# PR9001.net
KiCad netlist of a schematic drawn in EAGLE
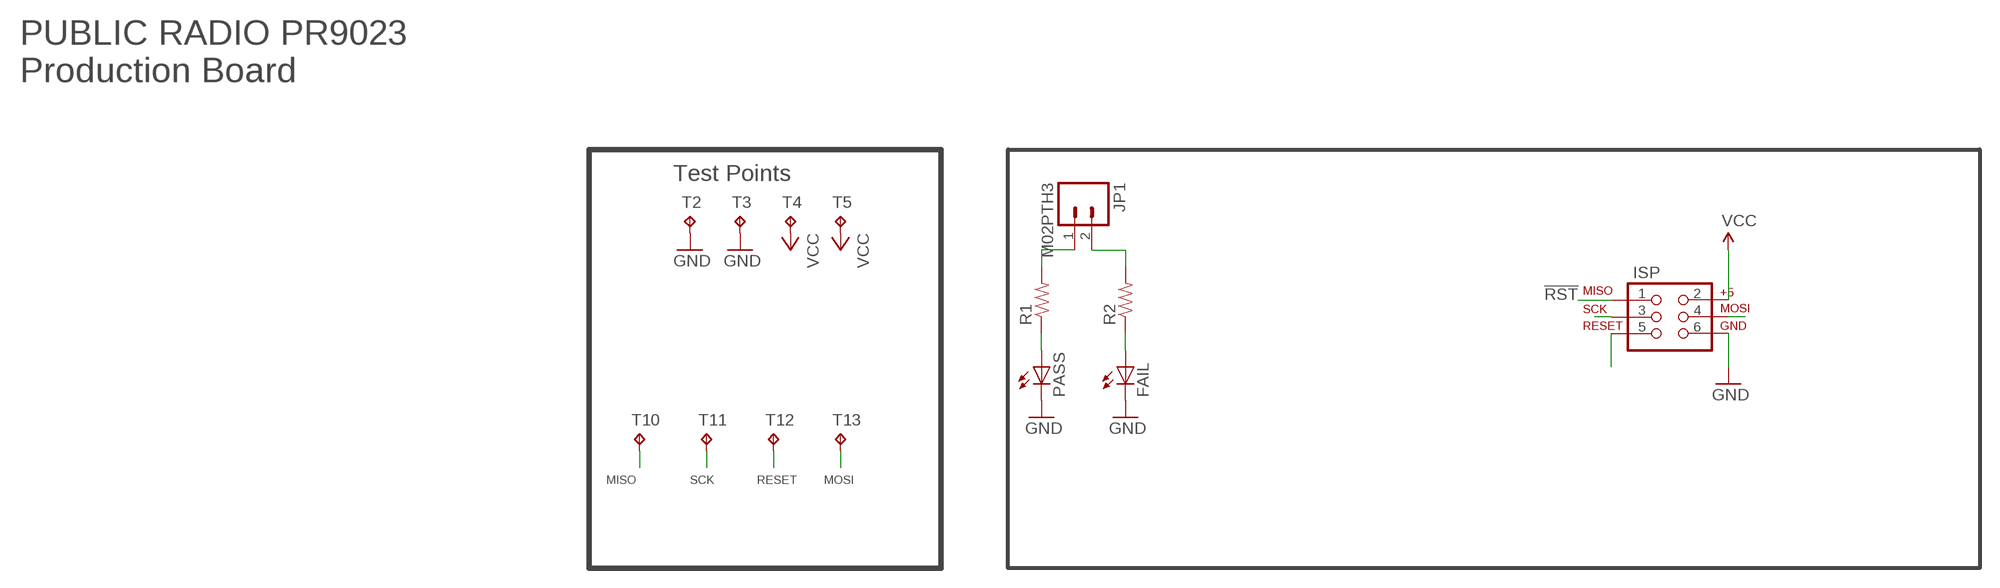
[diagram p0: schematic, sheet 1]

(export (version "E")
  (design (tool "Eeschema 10.0.6"))
  (components
    (comp (ref "FAIL")
      (value "LED5MM")
      (footprint "eagle-import:LED5MM")
      (libsource (lib "eagle-import") (part "LED5MM"))
    )
    (comp (ref "ISP")
      (value "AVR_SPI_PRG_6NS")
      (footprint "eagle-import:2X3-NS")
      (libsource (lib "eagle-import") (part "AVR_SPI_PRG_6NS"))
    )
    (comp (ref "JP1")
      (value "M02PTH3")
      (footprint "eagle-import:1X02_LONGPADS")
      (libsource (lib "eagle-import") (part "M02PTH3"))
    )
    (comp (ref "PASS")
      (value "LED5MM")
      (footprint "eagle-import:LED5MM")
      (libsource (lib "eagle-import") (part "LED5MM"))
    )
    (comp (ref "R1")
      (value "RESISTORPTH-1/4W-VERT")
      (footprint "eagle-import:AXIAL-0.1")
      (libsource (lib "eagle-import") (part "RESISTORPTH-1/4W-VERT"))
    )
    (comp (ref "R2")
      (value "RESISTORPTH-1/4W-VERT")
      (footprint "eagle-import:AXIAL-0.1")
      (libsource (lib "eagle-import") (part "RESISTORPTH-1/4W-VERT"))
    )
    (comp (ref "T2")
      (value "PR9001_TESTPOINT")
      (footprint "eagle-import:PR9001_TESTPOINT")
      (libsource (lib "eagle-import") (part "PR9001_TESTPOINT"))
    )
    (comp (ref "T3")
      (value "PR9001_TESTPOINT")
      (footprint "eagle-import:PR9001_TESTPOINT")
      (libsource (lib "eagle-import") (part "PR9001_TESTPOINT"))
    )
    (comp (ref "T4")
      (value "PR9001_TESTPOINT")
      (footprint "eagle-import:PR9001_TESTPOINT")
      (libsource (lib "eagle-import") (part "PR9001_TESTPOINT"))
    )
    (comp (ref "T5")
      (value "PR9001_TESTPOINT")
      (footprint "eagle-import:PR9001_TESTPOINT")
      (libsource (lib "eagle-import") (part "PR9001_TESTPOINT"))
    )
    (comp (ref "T10")
      (value "PR9001_TESTPOINT")
      (footprint "eagle-import:PR9001_TESTPOINT")
      (libsource (lib "eagle-import") (part "PR9001_TESTPOINT"))
    )
    (comp (ref "T11")
      (value "PR9001_TESTPOINT")
      (footprint "eagle-import:PR9001_TESTPOINT")
      (libsource (lib "eagle-import") (part "PR9001_TESTPOINT"))
    )
    (comp (ref "T12")
      (value "PR9001_TESTPOINT")
      (footprint "eagle-import:PR9001_TESTPOINT")
      (libsource (lib "eagle-import") (part "PR9001_TESTPOINT"))
    )
    (comp (ref "T13")
      (value "PR9001_TESTPOINT")
      (footprint "eagle-import:PR9001_TESTPOINT")
      (libsource (lib "eagle-import") (part "PR9001_TESTPOINT"))
    )
  )
  (nets
    (net (code "1") (name "/RESET") (class "Default")
      (node (ref "ISP") (pin "5") (pinfunction "5_5") (pintype "passive"))
      (node (ref "T12") (pin "P$1") (pinfunction "TP_P$1") (pintype "input"))
    )
    (net (code "2") (name "/SCLK") (class "Default")
      (node (ref "ISP") (pin "3") (pinfunction "3_3") (pintype "passive"))
      (node (ref "T11") (pin "P$1") (pinfunction "TP_P$1") (pintype "input"))
    )
    (net (code "3") (name "/SDIO") (class "Default")
      (node (ref "ISP") (pin "4") (pinfunction "4_4") (pintype "passive"))
      (node (ref "T13") (pin "P$1") (pinfunction "TP_P$1") (pintype "input"))
    )
    (net (code "4") (name "/~{RST}") (class "Default")
      (node (ref "ISP") (pin "1") (pinfunction "1_1") (pintype "passive"))
      (node (ref "T10") (pin "P$1") (pinfunction "TP_P$1") (pintype "input"))
    )
    (net (code "5") (name "GND") (class "Default")
      (node (ref "FAIL") (pin "K") (pinfunction "C_K") (pintype "passive"))
      (node (ref "ISP") (pin "6") (pinfunction "6_6") (pintype "passive"))
      (node (ref "PASS") (pin "K") (pinfunction "C_K") (pintype "passive"))
      (node (ref "T2") (pin "P$1") (pinfunction "TP_P$1") (pintype "input"))
      (node (ref "T3") (pin "P$1") (pinfunction "TP_P$1") (pintype "input"))
    )
    (net (code "6") (name "Net-(R1-1)") (class "Default")
      (node (ref "PASS") (pin "A") (pinfunction "A_A") (pintype "passive"))
      (node (ref "R1") (pin "P$1") (pinfunction "1_P$1") (pintype "passive"))
    )
    (net (code "7") (name "Net-(R1-2)") (class "Default")
      (node (ref "JP1") (pin "1") (pinfunction "1_1") (pintype "passive"))
      (node (ref "R1") (pin "P$2") (pinfunction "2_P$2") (pintype "passive"))
    )
    (net (code "8") (name "Net-(R2-1)") (class "Default")
      (node (ref "FAIL") (pin "A") (pinfunction "A_A") (pintype "passive"))
      (node (ref "R2") (pin "P$1") (pinfunction "1_P$1") (pintype "passive"))
    )
    (net (code "9") (name "Net-(R2-2)") (class "Default")
      (node (ref "JP1") (pin "2") (pinfunction "2_2") (pintype "passive"))
      (node (ref "R2") (pin "P$2") (pinfunction "2_P$2") (pintype "passive"))
    )
    (net (code "10") (name "VCC") (class "Default")
      (node (ref "ISP") (pin "2") (pinfunction "2_2") (pintype "passive"))
      (node (ref "T4") (pin "P$1") (pinfunction "TP_P$1") (pintype "input"))
      (node (ref "T5") (pin "P$1") (pinfunction "TP_P$1") (pintype "input"))
    )
  )
)
